# shield_romwriter.net
KiCad netlist of a schematic drawn in EAGLE
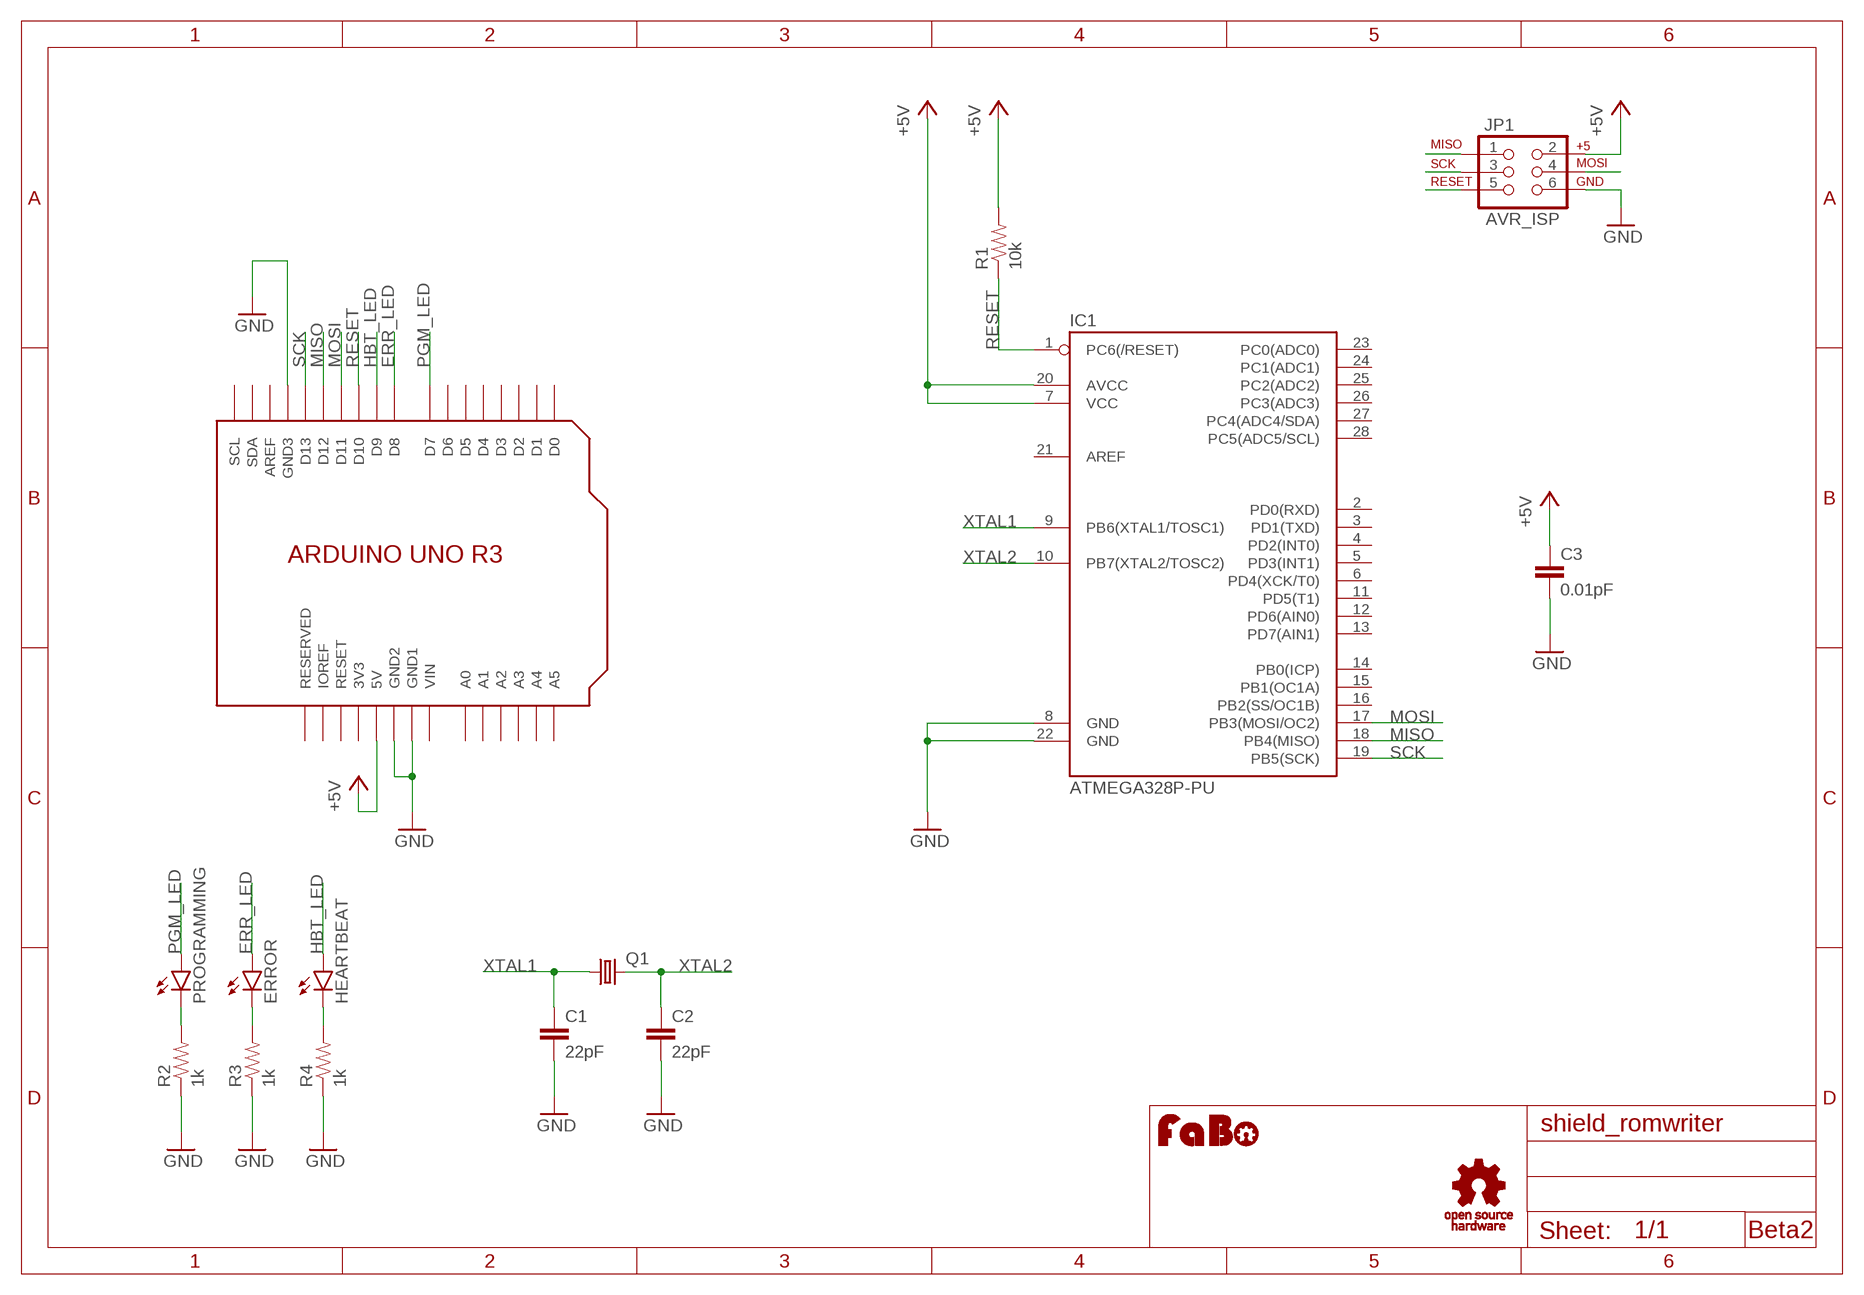
[diagram p0: schematic, sheet 1]

(export (version "E")
  (design (tool "Eeschema 10.0.6"))
  (components
    (comp (ref "C1")
      (value "22pF")
      (footprint "eagle-import:CAP-PTH-SMALL")
      (libsource (lib "eagle-import") (part "CAP-PTH-SMALL"))
    )
    (comp (ref "C2")
      (value "22pF")
      (footprint "eagle-import:CAP-PTH-SMALL")
      (libsource (lib "eagle-import") (part "CAP-PTH-SMALL"))
    )
    (comp (ref "C3")
      (value "0.01pF")
      (footprint "eagle-import:CAP-PTH-SMALL")
      (libsource (lib "eagle-import") (part "CAP-PTH-SMALL"))
    )
    (comp (ref "ERROR")
      (value "LED3MM")
      (footprint "eagle-import:LED3MM")
      (libsource (lib "eagle-import") (part "LED3MM"))
    )
    (comp (ref "HEARTBEAT")
      (value "LED3MM")
      (footprint "eagle-import:LED3MM")
      (libsource (lib "eagle-import") (part "LED3MM"))
    )
    (comp (ref "IC1")
      (value "ATMEGA328P-PU")
      (footprint "eagle-import:DIL28")
      (libsource (lib "eagle-import") (part "ATMEGA328P-PU"))
    )
    (comp (ref "JP1")
      (value "AVR_ISP")
      (footprint "eagle-import:2X3_LOCK")
      (libsource (lib "eagle-import") (part "AVR_SPI_PRG_62X3_LOCK"))
    )
    (comp (ref "PROGRAMMING")
      (value "LED3MM")
      (footprint "eagle-import:LED3MM")
      (libsource (lib "eagle-import") (part "LED3MM"))
    )
    (comp (ref "Q1")
      (value "CRYSTALHC49S")
      (footprint "eagle-import:HC49_S")
      (libsource (lib "eagle-import") (part "CRYSTALHC49S"))
    )
    (comp (ref "R1")
      (value "10k")
      (footprint "eagle-import:RES-AXL-REGULAR")
      (libsource (lib "eagle-import") (part "RES-PTH-REGULAR"))
    )
    (comp (ref "R2")
      (value "1k")
      (footprint "eagle-import:RES-AXL-REGULAR")
      (libsource (lib "eagle-import") (part "RES-PTH-REGULAR"))
    )
    (comp (ref "R3")
      (value "1k")
      (footprint "eagle-import:RES-AXL-REGULAR")
      (libsource (lib "eagle-import") (part "RES-PTH-REGULAR"))
    )
    (comp (ref "R4")
      (value "1k")
      (footprint "eagle-import:RES-AXL-REGULAR")
      (libsource (lib "eagle-import") (part "RES-PTH-REGULAR"))
    )
    (comp (ref "U$1")
      (value "LOGO_FABO-M")
      (footprint "eagle-import:LOGO_FABO_M")
      (libsource (lib "eagle-import") (part "LOGO_FABO-M"))
    )
    (comp (ref "U$3")
      (value "LOGO_OSHW_T-M")
      (footprint "eagle-import:LOGO_OSHW_T_M")
      (libsource (lib "eagle-import") (part "LOGO_OSHW_T-M"))
    )
    (comp (ref "U2")
      (value "ARDUINO_UNO_R3_SHIELD-NOLABEL")
      (footprint "eagle-import:ARDUINO_UNO_R3_NOLABEL")
      (libsource (lib "eagle-import") (part "ARDUINO_UNO_R3_SHIELD-NOLABEL"))
    )
  )
  (nets
    (net (code "1") (name "+5V") (class "Default")
      (node (ref "C3") (pin "1") (pinfunction "1_1") (pintype "passive"))
      (node (ref "IC1") (pin "20") (pinfunction "AVCC_20") (pintype "bidirectional"))
      (node (ref "IC1") (pin "7") (pinfunction "VCC_7") (pintype "bidirectional"))
      (node (ref "JP1") (pin "2") (pinfunction "2_2") (pintype "passive"))
      (node (ref "R1") (pin "P$2") (pinfunction "2_P$2") (pintype "passive"))
      (node (ref "U2") (pin "5V") (pinfunction "5V_5V") (pintype "power_in"))
    )
    (net (code "2") (name "/3V3") (class "Default")
      (node (ref "U2") (pin "3V3") (pinfunction "3V3_3V3") (pintype "power_in"))
    )
    (net (code "3") (name "/ERR_LED") (class "Default")
      (node (ref "ERROR") (pin "A") (pinfunction "A_A") (pintype "passive"))
      (node (ref "U2") (pin "D8") (pinfunction "D8_D8") (pintype "bidirectional"))
    )
    (net (code "4") (name "/HBT_LED") (class "Default")
      (node (ref "HEARTBEAT") (pin "A") (pinfunction "A_A") (pintype "passive"))
      (node (ref "U2") (pin "D9") (pinfunction "D9_D9") (pintype "bidirectional"))
    )
    (net (code "5") (name "/MISO") (class "Default")
      (node (ref "IC1") (pin "18") (pinfunction "PB4(MISO)_18") (pintype "bidirectional"))
      (node (ref "JP1") (pin "1") (pinfunction "1_1") (pintype "passive"))
      (node (ref "U2") (pin "D12") (pinfunction "D12_D12") (pintype "bidirectional"))
    )
    (net (code "6") (name "/MOSI") (class "Default")
      (node (ref "IC1") (pin "17") (pinfunction "PB3(MOSI/OC2)_17") (pintype "bidirectional"))
      (node (ref "JP1") (pin "4") (pinfunction "4_4") (pintype "passive"))
      (node (ref "U2") (pin "D11") (pinfunction "D11_D11") (pintype "bidirectional"))
    )
    (net (code "7") (name "/PGM_LED") (class "Default")
      (node (ref "PROGRAMMING") (pin "A") (pinfunction "A_A") (pintype "passive"))
      (node (ref "U2") (pin "D7") (pinfunction "D7_D7") (pintype "bidirectional"))
    )
    (net (code "8") (name "/RESET") (class "Default")
      (node (ref "IC1") (pin "1") (pinfunction "PC6(/RESET)_1") (pintype "bidirectional"))
      (node (ref "JP1") (pin "5") (pinfunction "5_5") (pintype "passive"))
      (node (ref "R1") (pin "P$1") (pinfunction "1_P$1") (pintype "passive"))
      (node (ref "U2") (pin "D10") (pinfunction "D10_D10") (pintype "bidirectional"))
    )
    (net (code "9") (name "/SCK") (class "Default")
      (node (ref "IC1") (pin "19") (pinfunction "PB5(SCK)_19") (pintype "bidirectional"))
      (node (ref "JP1") (pin "3") (pinfunction "3_3") (pintype "passive"))
      (node (ref "U2") (pin "D13") (pinfunction "D13_D13") (pintype "bidirectional"))
    )
    (net (code "10") (name "/VIN") (class "Default")
      (node (ref "U2") (pin "VIN") (pinfunction "VIN_VIN") (pintype "power_in"))
    )
    (net (code "11") (name "/XTAL1") (class "Default")
      (node (ref "C1") (pin "1") (pinfunction "1_1") (pintype "passive"))
      (node (ref "IC1") (pin "9") (pinfunction "PB6(XTAL1/TOSC1)_9") (pintype "bidirectional"))
      (node (ref "Q1") (pin "1") (pinfunction "1_1") (pintype "passive"))
    )
    (net (code "12") (name "/XTAL2") (class "Default")
      (node (ref "C2") (pin "1") (pinfunction "1_1") (pintype "passive"))
      (node (ref "IC1") (pin "10") (pinfunction "PB7(XTAL2/TOSC2)_10") (pintype "bidirectional"))
      (node (ref "Q1") (pin "2") (pinfunction "2_2") (pintype "passive"))
    )
    (net (code "13") (name "GND") (class "Default")
      (node (ref "C1") (pin "2") (pinfunction "2_2") (pintype "passive"))
      (node (ref "C2") (pin "2") (pinfunction "2_2") (pintype "passive"))
      (node (ref "C3") (pin "2") (pinfunction "2_2") (pintype "passive"))
      (node (ref "IC1") (pin "22") (pinfunction "GND_22") (pintype "bidirectional"))
      (node (ref "IC1") (pin "8") (pinfunction "GND_8") (pintype "bidirectional"))
      (node (ref "JP1") (pin "6") (pinfunction "6_6") (pintype "passive"))
      (node (ref "R2") (pin "P$1") (pinfunction "1_P$1") (pintype "passive"))
      (node (ref "R3") (pin "P$1") (pinfunction "1_P$1") (pintype "passive"))
      (node (ref "R4") (pin "P$1") (pinfunction "1_P$1") (pintype "passive"))
      (node (ref "U2") (pin "GND1") (pinfunction "GND1_GND1") (pintype "power_in"))
      (node (ref "U2") (pin "GND2") (pinfunction "GND2_GND2") (pintype "power_in"))
      (node (ref "U2") (pin "GND3") (pinfunction "GND3_GND3") (pintype "power_in"))
    )
    (net (code "14") (name "Net-(ERROR-C)") (class "Default")
      (node (ref "ERROR") (pin "K") (pinfunction "C_K") (pintype "passive"))
      (node (ref "R3") (pin "P$2") (pinfunction "2_P$2") (pintype "passive"))
    )
    (net (code "15") (name "Net-(HEARTBEAT-C)") (class "Default")
      (node (ref "HEARTBEAT") (pin "K") (pinfunction "C_K") (pintype "passive"))
      (node (ref "R4") (pin "P$2") (pinfunction "2_P$2") (pintype "passive"))
    )
    (net (code "16") (name "Net-(PROGRAMMING-C)") (class "Default")
      (node (ref "PROGRAMMING") (pin "K") (pinfunction "C_K") (pintype "passive"))
      (node (ref "R2") (pin "P$2") (pinfunction "2_P$2") (pintype "passive"))
    )
    (net (code "17") (name "unconnected-(IC1-AREF-Pad21)") (class "Default")
      (node (ref "IC1") (pin "21") (pinfunction "AREF_21") (pintype "bidirectional"))
    )
    (net (code "18") (name "unconnected-(IC1-PB0(ICP)-Pad14)") (class "Default")
      (node (ref "IC1") (pin "14") (pinfunction "PB0(ICP)_14") (pintype "bidirectional"))
    )
    (net (code "19") (name "unconnected-(IC1-PB1(OC1A)-Pad15)") (class "Default")
      (node (ref "IC1") (pin "15") (pinfunction "PB1(OC1A)_15") (pintype "bidirectional"))
    )
    (net (code "20") (name "unconnected-(IC1-PB2(SS{slash}OC1B)-Pad16)") (class "Default")
      (node (ref "IC1") (pin "16") (pinfunction "PB2(SS/OC1B)_16") (pintype "bidirectional"))
    )
    (net (code "21") (name "unconnected-(IC1-PC0(ADC0)-Pad23)") (class "Default")
      (node (ref "IC1") (pin "23") (pinfunction "PC0(ADC0)_23") (pintype "bidirectional"))
    )
    (net (code "22") (name "unconnected-(IC1-PC1(ADC1)-Pad24)") (class "Default")
      (node (ref "IC1") (pin "24") (pinfunction "PC1(ADC1)_24") (pintype "bidirectional"))
    )
    (net (code "23") (name "unconnected-(IC1-PC2(ADC2)-Pad25)") (class "Default")
      (node (ref "IC1") (pin "25") (pinfunction "PC2(ADC2)_25") (pintype "bidirectional"))
    )
    (net (code "24") (name "unconnected-(IC1-PC3(ADC3)-Pad26)") (class "Default")
      (node (ref "IC1") (pin "26") (pinfunction "PC3(ADC3)_26") (pintype "bidirectional"))
    )
    (net (code "25") (name "unconnected-(IC1-PC4(ADC4{slash}SDA)-Pad27)") (class "Default")
      (node (ref "IC1") (pin "27") (pinfunction "PC4(ADC4/SDA)_27") (pintype "bidirectional"))
    )
    (net (code "26") (name "unconnected-(IC1-PC5(ADC5{slash}SCL)-Pad28)") (class "Default")
      (node (ref "IC1") (pin "28") (pinfunction "PC5(ADC5/SCL)_28") (pintype "bidirectional"))
    )
    (net (code "27") (name "unconnected-(IC1-PD0(RXD)-Pad2)") (class "Default")
      (node (ref "IC1") (pin "2") (pinfunction "PD0(RXD)_2") (pintype "bidirectional"))
    )
    (net (code "28") (name "unconnected-(IC1-PD1(TXD)-Pad3)") (class "Default")
      (node (ref "IC1") (pin "3") (pinfunction "PD1(TXD)_3") (pintype "bidirectional"))
    )
    (net (code "29") (name "unconnected-(IC1-PD2(INT0)-Pad4)") (class "Default")
      (node (ref "IC1") (pin "4") (pinfunction "PD2(INT0)_4") (pintype "bidirectional"))
    )
    (net (code "30") (name "unconnected-(IC1-PD3(INT1)-Pad5)") (class "Default")
      (node (ref "IC1") (pin "5") (pinfunction "PD3(INT1)_5") (pintype "bidirectional"))
    )
    (net (code "31") (name "unconnected-(IC1-PD4(XCK{slash}T0)-Pad6)") (class "Default")
      (node (ref "IC1") (pin "6") (pinfunction "PD4(XCK/T0)_6") (pintype "bidirectional"))
    )
    (net (code "32") (name "unconnected-(IC1-PD5(T1)-Pad11)") (class "Default")
      (node (ref "IC1") (pin "11") (pinfunction "PD5(T1)_11") (pintype "bidirectional"))
    )
    (net (code "33") (name "unconnected-(IC1-PD6(AIN0)-Pad12)") (class "Default")
      (node (ref "IC1") (pin "12") (pinfunction "PD6(AIN0)_12") (pintype "bidirectional"))
    )
    (net (code "34") (name "unconnected-(IC1-PD7(AIN1)-Pad13)") (class "Default")
      (node (ref "IC1") (pin "13") (pinfunction "PD7(AIN1)_13") (pintype "bidirectional"))
    )
    (net (code "35") (name "unconnected-(U2-PadA0)") (class "Default")
      (node (ref "U2") (pin "A0") (pinfunction "A0_A0") (pintype "bidirectional"))
    )
    (net (code "36") (name "unconnected-(U2-PadA1)") (class "Default")
      (node (ref "U2") (pin "A1") (pinfunction "A1_A1") (pintype "bidirectional"))
    )
    (net (code "37") (name "unconnected-(U2-PadA2)") (class "Default")
      (node (ref "U2") (pin "A2") (pinfunction "A2_A2") (pintype "bidirectional"))
    )
    (net (code "38") (name "unconnected-(U2-PadA3)") (class "Default")
      (node (ref "U2") (pin "A3") (pinfunction "A3_A3") (pintype "bidirectional"))
    )
    (net (code "39") (name "unconnected-(U2-PadA4)") (class "Default")
      (node (ref "U2") (pin "A4") (pinfunction "A4_A4") (pintype "bidirectional"))
    )
    (net (code "40") (name "unconnected-(U2-PadA5)") (class "Default")
      (node (ref "U2") (pin "A5") (pinfunction "A5_A5") (pintype "bidirectional"))
    )
    (net (code "41") (name "unconnected-(U2-PadAREF)") (class "Default")
      (node (ref "U2") (pin "AREF") (pinfunction "AREF_AREF") (pintype "bidirectional"))
    )
    (net (code "42") (name "unconnected-(U2-PadD0)") (class "Default")
      (node (ref "U2") (pin "D0") (pinfunction "D0_D0") (pintype "bidirectional"))
    )
    (net (code "43") (name "unconnected-(U2-PadD1)") (class "Default")
      (node (ref "U2") (pin "D1") (pinfunction "D1_D1") (pintype "bidirectional"))
    )
    (net (code "44") (name "unconnected-(U2-PadD2)") (class "Default")
      (node (ref "U2") (pin "D2") (pinfunction "D2_D2") (pintype "bidirectional"))
    )
    (net (code "45") (name "unconnected-(U2-PadD3)") (class "Default")
      (node (ref "U2") (pin "D3") (pinfunction "D3_D3") (pintype "bidirectional"))
    )
    (net (code "46") (name "unconnected-(U2-PadD4)") (class "Default")
      (node (ref "U2") (pin "D4") (pinfunction "D4_D4") (pintype "bidirectional"))
    )
    (net (code "47") (name "unconnected-(U2-PadD5)") (class "Default")
      (node (ref "U2") (pin "D5") (pinfunction "D5_D5") (pintype "bidirectional"))
    )
    (net (code "48") (name "unconnected-(U2-PadD6)") (class "Default")
      (node (ref "U2") (pin "D6") (pinfunction "D6_D6") (pintype "bidirectional"))
    )
    (net (code "49") (name "unconnected-(U2-PadIOREF)") (class "Default")
      (node (ref "U2") (pin "IOREF") (pinfunction "IOREF_IOREF") (pintype "output"))
    )
    (net (code "50") (name "unconnected-(U2-PadRESERVED)") (class "Default")
      (node (ref "U2") (pin "RESERVED") (pinfunction "RESERVED_RESERVED") (pintype "no_connect"))
    )
    (net (code "51") (name "unconnected-(U2-PadRESET)") (class "Default")
      (node (ref "U2") (pin "RESET") (pinfunction "RESET_RESET") (pintype "bidirectional"))
    )
    (net (code "52") (name "unconnected-(U2-PadSCL)") (class "Default")
      (node (ref "U2") (pin "SCL") (pinfunction "SCL_SCL") (pintype "bidirectional"))
    )
    (net (code "53") (name "unconnected-(U2-PadSDA)") (class "Default")
      (node (ref "U2") (pin "SDA") (pinfunction "SDA_SDA") (pintype "bidirectional"))
    )
  )
)
